# 05-Display.net
KiCad netlist of a schematic drawn in Altium Designer
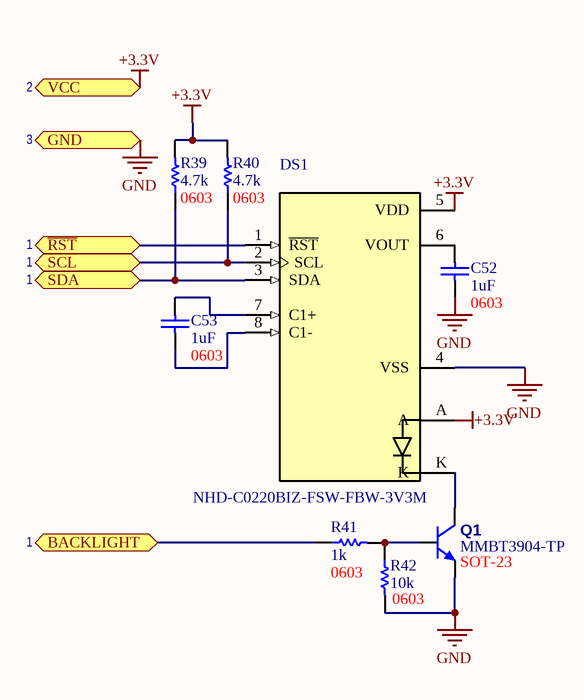
[diagram p0: 05-Display.SchDoc]

(export (version "E")
  (design (tool "Eeschema 10.0.6"))
  (components
    (comp (ref "C52")
      (value "1uF")
      (footprint "C0603")
      (description "Capacitor (Semiconductor SIM Model)")
      (fields
        (field (name "MANUFACTURER PART NUMBER") "CL10A105KQ8NNNC")
        (field (name "PACKAGEREFERENCE") "0603")
      )
      (libsource (lib "Miscellaneous Devices") (part "Cap Semi"))
    )
    (comp (ref "C53")
      (value "1uF")
      (footprint "C0603")
      (description "Capacitor (Semiconductor SIM Model)")
      (fields
        (field (name "MANUFACTURER PART NUMBER") "CL10A105KQ8NNNC")
        (field (name "PACKAGEREFERENCE") "0603")
      )
      (libsource (lib "Miscellaneous Devices") (part "Cap Semi"))
    )
    (comp (ref "DS1")
      (value "NHD-C0220BIZ-FSW-FBW-3V3M")
      (footprint "NHD-C0220BIZ-FSW-FBW-3V3M")
      (description "n LCD COG CHAR 2X20 WH TRANSFL")
      (libsource (lib "Library") (part "NHD-C0220BIZ-FSW-FBW-3V3M"))
    )
    (comp (ref "Q1")
      (value "MMBT3904-TP")
      (footprint "SOT23-3")
      (description "TRANS NPN 40V 0.2A SOT-23")
      (fields (field (name "PACKAGEREFERENCE") "SOT-23"))
      (libsource (lib "schematic_library") (part "MMBT3904"))
    )
    (comp (ref "R39")
      (value "4.7k")
      (footprint "R0603")
      (description "Resistor")
      (fields
        (field (name "MANUFACTURER PART NUMBER") "RMCF0603JT4K70")
        (field (name "PACKAGEREFERENCE") "0603")
      )
      (libsource (lib "Miscellaneous Devices") (part "Res1"))
    )
    (comp (ref "R40")
      (value "4.7k")
      (footprint "R0603")
      (description "Resistor")
      (fields
        (field (name "MANUFACTURER PART NUMBER") "RMCF0603JT4K70")
        (field (name "PACKAGEREFERENCE") "0603")
      )
      (libsource (lib "Miscellaneous Devices") (part "Res1"))
    )
    (comp (ref "R41")
      (value "1k")
      (footprint "R0603")
      (description "Resistor")
      (fields
        (field (name "MANUFACTURER PART NUMBER") "RMCF0603FG1K00")
        (field (name "PACKAGEREFERENCE") "0603")
      )
      (libsource (lib "Miscellaneous Devices") (part "Res1"))
    )
    (comp (ref "R42")
      (value "10k")
      (footprint "R0603")
      (description "Resistor")
      (fields
        (field (name "MANUFACTURER PART NUMBER") "RMCF0603FT10K0")
        (field (name "PACKAGEREFERENCE") "0603")
      )
      (libsource (lib "Miscellaneous Devices") (part "Res1"))
    )
  )
  (nets
    (net (code "1") (name "+3.3V") (class "Default")
      (node (ref "DS1") (pin "5") (pinfunction "VDD_5") (pintype "power_in"))
      (node (ref "DS1") (pin "A") (pinfunction "A_A") (pintype "passive"))
      (node (ref "R39") (pin "2") (pinfunction "2_2") (pintype "passive"))
      (node (ref "R40") (pin "2") (pinfunction "2_2") (pintype "passive"))
    )
    (net (code "2") (name "/BACKLIGHT") (class "Default")
      (node (ref "R41") (pin "1") (pinfunction "1_1") (pintype "passive"))
    )
    (net (code "3") (name "/SCL") (class "Default")
      (node (ref "DS1") (pin "2") (pinfunction "SCL_2") (pintype "input"))
      (node (ref "R40") (pin "1") (pinfunction "1_1") (pintype "passive"))
    )
    (net (code "4") (name "/SDA") (class "Default")
      (node (ref "DS1") (pin "3") (pinfunction "SDA_3") (pintype "input"))
      (node (ref "R39") (pin "1") (pinfunction "1_1") (pintype "passive"))
    )
    (net (code "5") (name "/~{RST}") (class "Default")
      (node (ref "DS1") (pin "1") (pinfunction "~{RST}_1") (pintype "input"))
    )
    (net (code "6") (name "GND") (class "Default")
      (node (ref "C52") (pin "2") (pinfunction "2_2") (pintype "passive"))
      (node (ref "DS1") (pin "4") (pinfunction "VSS_4") (pintype "passive"))
      (node (ref "Q1") (pin "1") (pinfunction "E_1") (pintype "passive"))
      (node (ref "R42") (pin "2") (pinfunction "2_2") (pintype "passive"))
    )
    (net (code "7") (name "Net-(DS1-C1+)") (class "Default")
      (node (ref "C53") (pin "1") (pinfunction "1_1") (pintype "passive"))
      (node (ref "DS1") (pin "7") (pinfunction "C1+_7") (pintype "input"))
    )
    (net (code "8") (name "Net-(DS1-C1-)") (class "Default")
      (node (ref "C53") (pin "2") (pinfunction "2_2") (pintype "passive"))
      (node (ref "DS1") (pin "8") (pinfunction "C1-_8") (pintype "input"))
    )
    (net (code "9") (name "Net-(DS1-VOUT)") (class "Default")
      (node (ref "C52") (pin "1") (pinfunction "1_1") (pintype "passive"))
      (node (ref "DS1") (pin "6") (pinfunction "VOUT_6") (pintype "power_in"))
    )
    (net (code "10") (name "Net-(Q1-B)") (class "Default")
      (node (ref "Q1") (pin "2") (pinfunction "B_2") (pintype "passive"))
      (node (ref "R41") (pin "2") (pinfunction "2_2") (pintype "passive"))
      (node (ref "R42") (pin "1") (pinfunction "1_1") (pintype "passive"))
    )
    (net (code "11") (name "Net-(Q1-C)") (class "Default")
      (node (ref "DS1") (pin "K") (pinfunction "K_K") (pintype "passive"))
      (node (ref "Q1") (pin "3") (pinfunction "C_3") (pintype "passive"))
    )
  )
)
